# Sheet3.net
KiCad netlist of a schematic drawn in Altium Designer
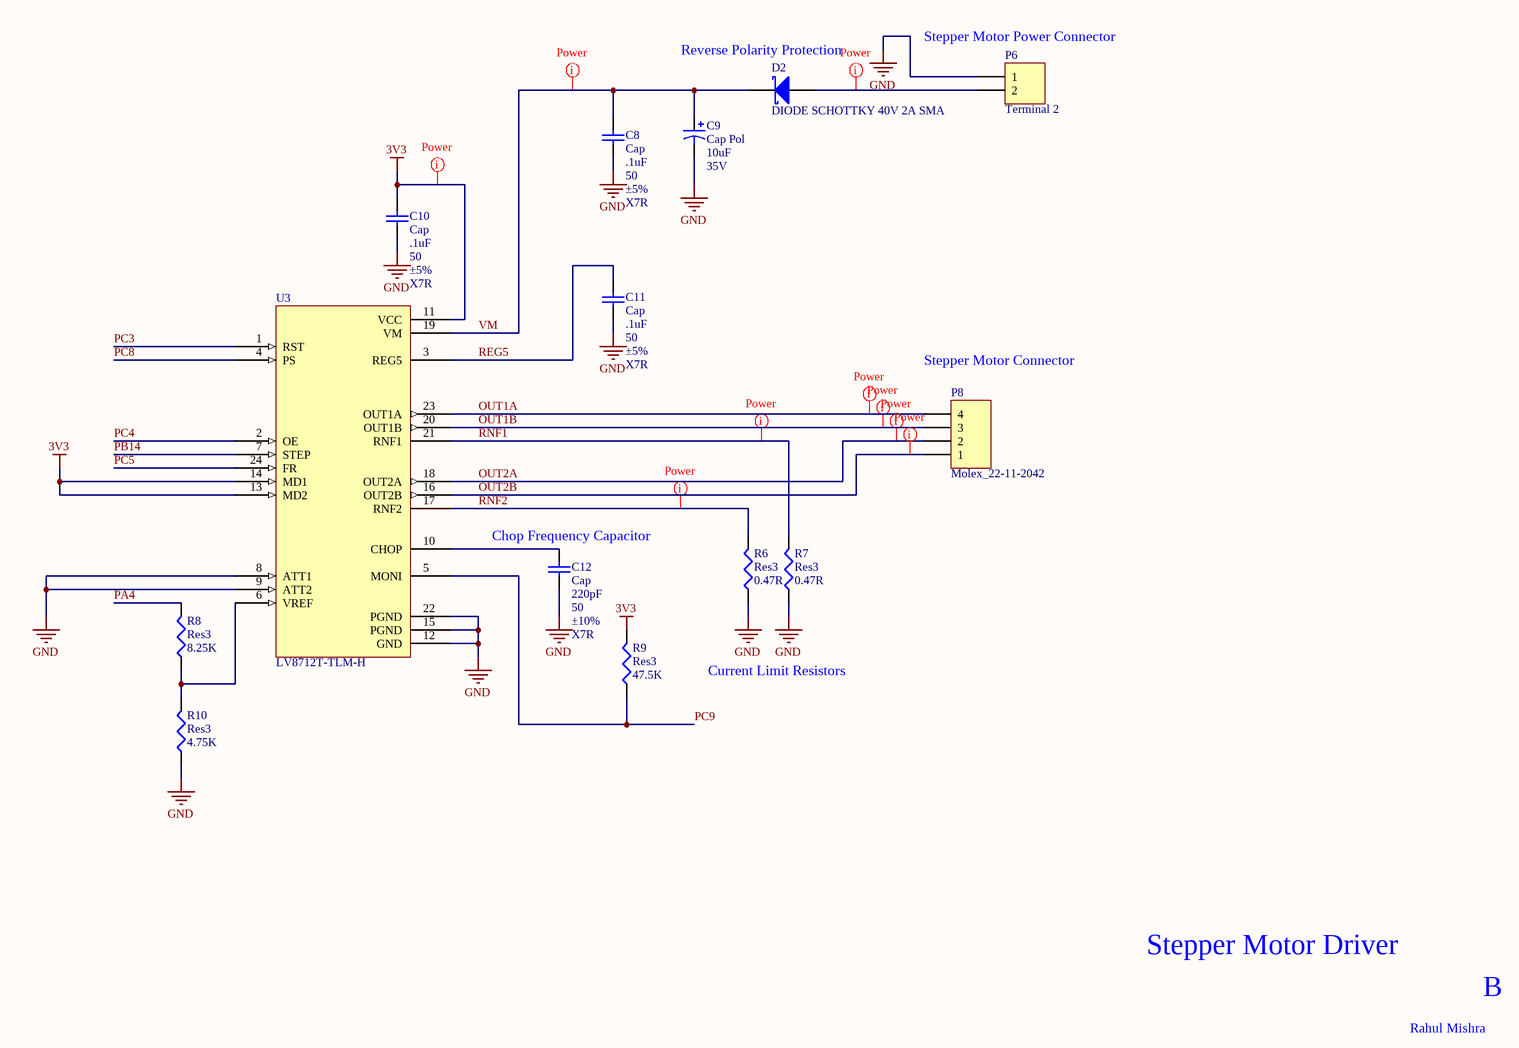
[diagram p0: Sheet3.SchDoc]

(export (version "E")
  (design (tool "Eeschema 10.0.6"))
  (components
    (comp (ref "C8")
      (value "Cap")
      (footprint "CAPC2012X09M")
      (description "CAP CER .1uF 50v X7R 0805")
      (fields
        (field (name "ALTIUM_VALUE") ".1uF")
        (field (name "WV") "50")
        (field (name "TOLERANCE") "±5%")
        (field (name "TYPE") "X7R")
        (field (name "MPN") "C0805C104J5RACTU")
      )
      (libsource (lib "esd_library") (part "CAP-X7R-.1uF-50V-±5%"))
    )
    (comp (ref "C9")
      (value "Cap Pol")
      (footprint "CAPACITOR_5MM")
      (description "CAP 85C 10uF ±20% 35V WX Series Aluminum Electrolytic")
      (fields
        (field (name "ALTIUM_VALUE") "10uF")
        (field (name "VOLTAGE") "35V")
        (field (name "MPN") "UWX1V100MCL1GB")
      )
      (libsource (lib "esd_library") (part "Cap Polar-10uF-35V"))
    )
    (comp (ref "C10")
      (value "Cap")
      (footprint "CAPC2012X09M")
      (description "CAP CER .1uF 50v X7R 0805")
      (fields
        (field (name "ALTIUM_VALUE") ".1uF")
        (field (name "WV") "50")
        (field (name "TOLERANCE") "±5%")
        (field (name "TYPE") "X7R")
        (field (name "MPN") "C0805C104J5RACTU")
      )
      (libsource (lib "esd_library") (part "CAP-X7R-.1uF-50V-±5%"))
    )
    (comp (ref "C11")
      (value "Cap")
      (footprint "CAPC2012X09M")
      (description "CAP CER .1uF 50v X7R 0805")
      (fields
        (field (name "ALTIUM_VALUE") ".1uF")
        (field (name "WV") "50")
        (field (name "TOLERANCE") "±5%")
        (field (name "TYPE") "X7R")
        (field (name "MPN") "C0805C104J5RACTU")
      )
      (libsource (lib "esd_library") (part "CAP-X7R-.1uF-50V-±5%"))
    )
    (comp (ref "C12")
      (value "Cap")
      (footprint "CAPC2012X09M")
      (description "CAP CER 220pF 50v X7R 0805")
      (fields
        (field (name "ALTIUM_VALUE") "220pF")
        (field (name "WV") "50")
        (field (name "TOLERANCE") "±10%")
        (field (name "TYPE") "X7R")
        (field (name "MPN") "C0805C221K5RACTU")
      )
      (libsource (lib "esd_library") (part "CAP-X7R-220pF-50V-±10%"))
    )
    (comp (ref "D2")
      (value "DIODE SCHOTTKY 40V 2A SMA")
      (footprint "DIOM4326X23M")
      (description "Schottky Rectifier")
      (fields (field (name "MPN") "B240A-13-F"))
      (libsource (lib "esd_library") (part "DIODE SCHOTTKY 40V 2A SMA"))
    )
    (comp (ref "P6")
      (value "Terminal 2")
      (footprint "TYCO_282841_2")
      (description "Terminal, 2-Pin")
      (fields (field (name "MPN") "282841-2") (field (name "PUBLISHER") "Altium Limited"))
      (libsource (lib "esd_library") (part "Terminal 2"))
    )
    (comp (ref "P8")
      (value "Molex_22-11-2042")
      (footprint "MOLEX-22-11-2042")
      (description "CONN HEADER 4POS .100 VERT GOLD")
      (fields (field (name "MPN") "0022112042"))
      (libsource (lib "esd_library") (part "Molex_22-11-2042"))
    )
    (comp (ref "R6")
      (value "Res3")
      (footprint "RESC3125X07M")
      (description "RES SMD 0.47OHM 5% 1W 1210")
      (fields (field (name "MPN") "RCWE1210R470FKEA") (field (name "ALTIUM_VALUE") "0.47R"))
      (libsource (lib "esd_library") (part "Resistor_0.47R_1W"))
    )
    (comp (ref "R7")
      (value "Res3")
      (footprint "RESC3125X07M")
      (description "RES SMD 0.47OHM 5% 1W 1210")
      (fields (field (name "MPN") "RCWE1210R470FKEA") (field (name "ALTIUM_VALUE") "0.47R"))
      (libsource (lib "esd_library") (part "Resistor_0.47R_1W"))
    )
    (comp (ref "R8")
      (value "Res3")
      (footprint "RESC2112X05M")
      (description "RES SMD 8.25K OHM 1% 1/8W 0805")
      (fields (field (name "ALTIUM_VALUE") "8.25K") (field (name "MPN") "CRCW08058K25FKEA"))
      (libsource (lib "esd_library") (part "Resistor_8.25K"))
    )
    (comp (ref "R9")
      (value "Res3")
      (footprint "RESC2112X05M")
      (description "RES SMD 47.5K OHM 1% 1/8W 0805")
      (fields (field (name "ALTIUM_VALUE") "47.5K") (field (name "MPN") "CRCW080547K5FKEA"))
      (libsource (lib "esd_library") (part "Resistor_47.5K"))
    )
    (comp (ref "R10")
      (value "Res3")
      (footprint "RESC2112X05M")
      (description "RES SMD 4.75K OHM 1% 1/8W 0805")
      (fields (field (name "ALTIUM_VALUE") "4.75K") (field (name "MPN") "CRCW08054K75FKEA"))
      (libsource (lib "esd_library") (part "Resistor_4.75K"))
    )
    (comp (ref "U3")
      (value "LV8712T-TLM-H")
      (footprint "ONSEMITSSOP50P640X120-24M")
      (description "IC MOTOR DRIVER PAR 24TSSOP")
      (libsource (lib "esd_library") (part "LV8712T-TLM-H"))
    )
  )
  (nets
    (net (code "1") (name "/OUT1A") (class "Default")
      (node (ref "P8") (pin "4") (pinfunction "4_4") (pintype "passive"))
      (node (ref "U3") (pin "23") (pinfunction "OUT1A_23") (pintype "output"))
    )
    (net (code "2") (name "/OUT1B") (class "Default")
      (node (ref "P8") (pin "3") (pinfunction "3_3") (pintype "passive"))
      (node (ref "U3") (pin "20") (pinfunction "OUT1B_20") (pintype "output"))
    )
    (net (code "3") (name "/OUT2A") (class "Default")
      (node (ref "P8") (pin "2") (pinfunction "2_2") (pintype "passive"))
      (node (ref "U3") (pin "18") (pinfunction "OUT2A_18") (pintype "output"))
    )
    (net (code "4") (name "/OUT2B") (class "Default")
      (node (ref "P8") (pin "1") (pinfunction "1_1") (pintype "passive"))
      (node (ref "U3") (pin "16") (pinfunction "OUT2B_16") (pintype "output"))
    )
    (net (code "5") (name "/PA4") (class "Default")
      (node (ref "R8") (pin "2") (pinfunction "2_2") (pintype "passive"))
    )
    (net (code "6") (name "/PB14") (class "Default")
      (node (ref "U3") (pin "7") (pinfunction "STEP_7") (pintype "input"))
    )
    (net (code "7") (name "/PC3") (class "Default")
      (node (ref "U3") (pin "1") (pinfunction "RST_1") (pintype "input"))
    )
    (net (code "8") (name "/PC4") (class "Default")
      (node (ref "U3") (pin "2") (pinfunction "OE_2") (pintype "input"))
    )
    (net (code "9") (name "/PC5") (class "Default")
      (node (ref "U3") (pin "24") (pinfunction "FR_24") (pintype "input"))
    )
    (net (code "10") (name "/PC8") (class "Default")
      (node (ref "U3") (pin "4") (pinfunction "PS_4") (pintype "input"))
    )
    (net (code "11") (name "/PC9") (class "Default")
      (node (ref "R9") (pin "1") (pinfunction "1_1") (pintype "passive"))
      (node (ref "U3") (pin "5") (pinfunction "MONI_5") (pintype "open_collector"))
    )
    (net (code "12") (name "/REG5") (class "Default")
      (node (ref "C11") (pin "2") (pinfunction "2_2") (pintype "passive"))
      (node (ref "U3") (pin "3") (pinfunction "REG5_3") (pintype "power_in"))
    )
    (net (code "13") (name "/RNF1") (class "Default")
      (node (ref "R7") (pin "2") (pinfunction "2_2") (pintype "passive"))
      (node (ref "U3") (pin "21") (pinfunction "RNF1_21") (pintype "passive"))
    )
    (net (code "14") (name "/RNF2") (class "Default")
      (node (ref "R6") (pin "2") (pinfunction "2_2") (pintype "passive"))
      (node (ref "U3") (pin "17") (pinfunction "RNF2_17") (pintype "passive"))
    )
    (net (code "15") (name "/VM") (class "Default")
      (node (ref "C8") (pin "2") (pinfunction "2_2") (pintype "passive"))
      (node (ref "C9") (pin "1") (pinfunction "1_1") (pintype "passive"))
      (node (ref "D2") (pin "1") (pinfunction "K_1") (pintype "passive"))
      (node (ref "U3") (pin "19") (pinfunction "VM_19") (pintype "power_in"))
    )
    (net (code "16") (name "3V3") (class "Default")
      (node (ref "C10") (pin "2") (pinfunction "2_2") (pintype "passive"))
      (node (ref "R9") (pin "2") (pinfunction "2_2") (pintype "passive"))
      (node (ref "U3") (pin "11") (pinfunction "VCC_11") (pintype "power_in"))
      (node (ref "U3") (pin "13") (pinfunction "MD2_13") (pintype "input"))
      (node (ref "U3") (pin "14") (pinfunction "MD1_14") (pintype "input"))
    )
    (net (code "17") (name "GND") (class "Default")
      (node (ref "C10") (pin "1") (pinfunction "1_1") (pintype "passive"))
      (node (ref "C11") (pin "1") (pinfunction "1_1") (pintype "passive"))
      (node (ref "C12") (pin "1") (pinfunction "1_1") (pintype "passive"))
      (node (ref "C8") (pin "1") (pinfunction "1_1") (pintype "passive"))
      (node (ref "C9") (pin "2") (pinfunction "2_2") (pintype "passive"))
      (node (ref "P6") (pin "1") (pinfunction "1_1") (pintype "passive"))
      (node (ref "R10") (pin "1") (pinfunction "1_1") (pintype "passive"))
      (node (ref "R6") (pin "1") (pinfunction "1_1") (pintype "passive"))
      (node (ref "R7") (pin "1") (pinfunction "1_1") (pintype "passive"))
      (node (ref "U3") (pin "12") (pinfunction "GND_12") (pintype "power_in"))
      (node (ref "U3") (pin "15") (pinfunction "PGND_15") (pintype "power_in"))
      (node (ref "U3") (pin "22") (pinfunction "PGND_22") (pintype "power_in"))
      (node (ref "U3") (pin "8") (pinfunction "ATT1_8") (pintype "input"))
      (node (ref "U3") (pin "9") (pinfunction "ATT2_9") (pintype "input"))
    )
    (net (code "18") (name "Net-(D2-A)") (class "Default")
      (node (ref "D2") (pin "2") (pinfunction "A_2") (pintype "passive"))
      (node (ref "P6") (pin "2") (pinfunction "2_2") (pintype "passive"))
    )
    (net (code "19") (name "Net-(U3-CHOP)") (class "Default")
      (node (ref "C12") (pin "2") (pinfunction "2_2") (pintype "passive"))
      (node (ref "U3") (pin "10") (pinfunction "CHOP_10") (pintype "passive"))
    )
    (net (code "20") (name "Net-(U3-VREF)") (class "Default")
      (node (ref "R10") (pin "2") (pinfunction "2_2") (pintype "passive"))
      (node (ref "R8") (pin "1") (pinfunction "1_1") (pintype "passive"))
      (node (ref "U3") (pin "6") (pinfunction "VREF_6") (pintype "input"))
    )
  )
)
